# Obstacle_Bluetooth_V1_0.net
KiCad netlist of a schematic drawn in EAGLE
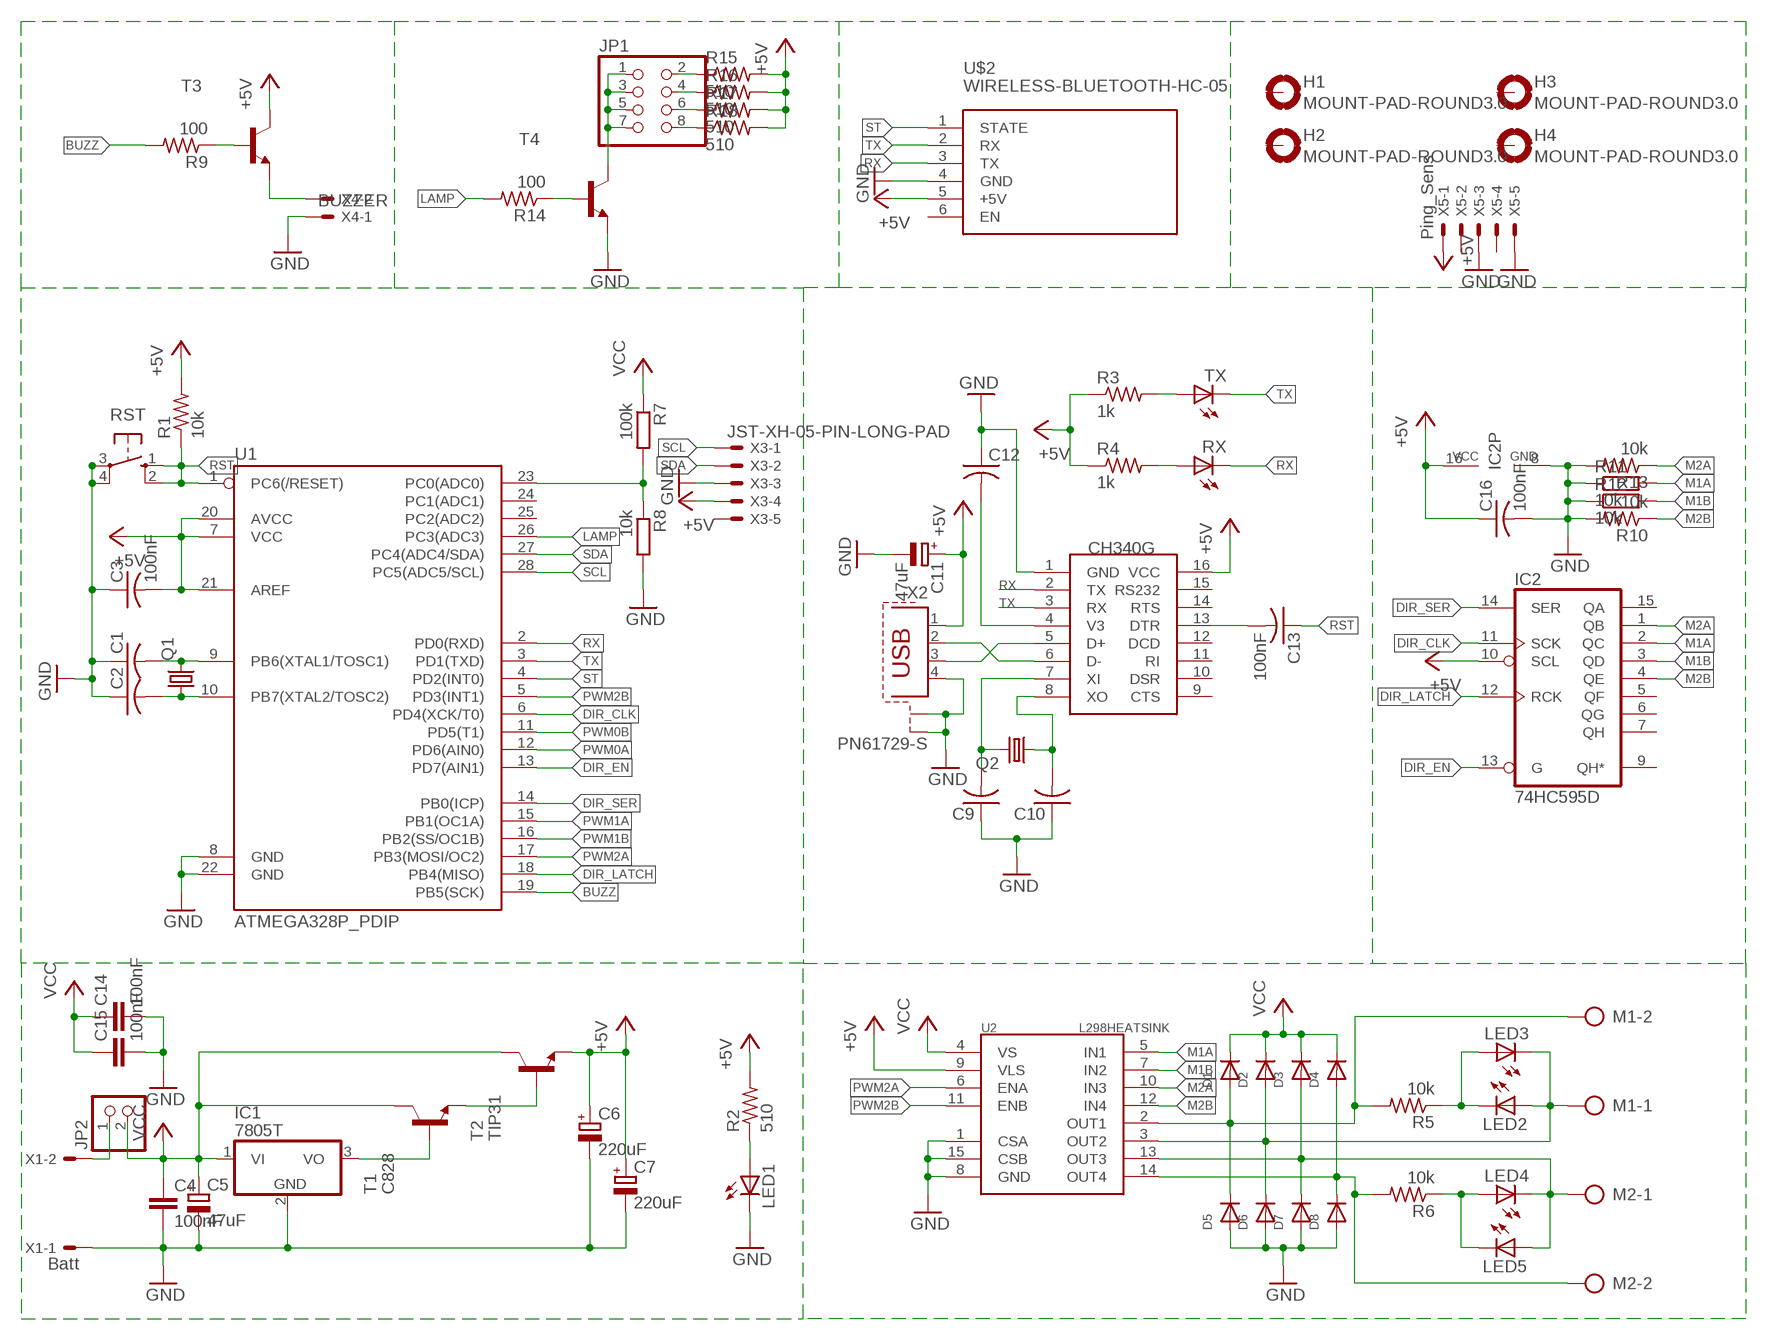
[diagram p0: schematic, sheet 1]

(export (version "E")
  (design (tool "Eeschema 10.0.6"))
  (components
    (comp (ref "C1")
      (value "C-USC0603K")
      (footprint "eagle-import:C0603K")
      (libsource (lib "eagle-import") (part "C-USC0603K"))
    )
    (comp (ref "C2")
      (value "C-USC0603K")
      (footprint "eagle-import:C0603K")
      (libsource (lib "eagle-import") (part "C-USC0603K"))
    )
    (comp (ref "C3")
      (value "100nF")
      (footprint "eagle-import:C0603K")
      (libsource (lib "eagle-import") (part "C-USC0603K"))
    )
    (comp (ref "C4")
      (value "100nF")
      (footprint "eagle-import:C5B2.5")
      (libsource (lib "eagle-import") (part "C5/2.5"))
    )
    (comp (ref "C5")
      (value "47uF")
      (footprint "eagle-import:E2,5-7")
      (libsource (lib "eagle-import") (part "CPOL-EUE2.5-7"))
    )
    (comp (ref "C6")
      (value "220uF")
      (footprint "eagle-import:E2,5-5")
      (libsource (lib "eagle-import") (part "CPOL-EUE2.5-5"))
    )
    (comp (ref "C7")
      (value "220uF")
      (footprint "eagle-import:E2,5-5")
      (libsource (lib "eagle-import") (part "CPOL-EUE2.5-5"))
    )
    (comp (ref "C9")
      (value "C-USC0603K")
      (footprint "eagle-import:C0603K")
      (libsource (lib "eagle-import") (part "C-USC0603K"))
    )
    (comp (ref "C10")
      (value "C-USC0603K")
      (footprint "eagle-import:C0603K")
      (libsource (lib "eagle-import") (part "C-USC0603K"))
    )
    (comp (ref "C11")
      (value "47uF")
      (footprint "eagle-import:E2,5-7")
      (libsource (lib "eagle-import") (part "CPOL-EUE2.5-7"))
    )
    (comp (ref "C12")
      (value "C-USC0603K")
      (footprint "eagle-import:C0603K")
      (libsource (lib "eagle-import") (part "C-USC0603K"))
    )
    (comp (ref "C13")
      (value "100nF")
      (footprint "eagle-import:C0603K")
      (libsource (lib "eagle-import") (part "C-USC0603K"))
    )
    (comp (ref "C14")
      (value "100nF")
      (footprint "eagle-import:C5B2.5")
      (libsource (lib "eagle-import") (part "C5/2.5"))
    )
    (comp (ref "C15")
      (value "100nF")
      (footprint "eagle-import:C5B2.5")
      (libsource (lib "eagle-import") (part "C5/2.5"))
    )
    (comp (ref "C16")
      (value "100nF")
      (footprint "eagle-import:C0603K")
      (libsource (lib "eagle-import") (part "C-USC0603K"))
    )
    (comp (ref "D1")
      (value "DIODESMA")
      (footprint "eagle-import:SMADIODE")
      (libsource (lib "eagle-import") (part "DIODESMA"))
    )
    (comp (ref "D2")
      (value "DIODESMA")
      (footprint "eagle-import:SMADIODE")
      (libsource (lib "eagle-import") (part "DIODESMA"))
    )
    (comp (ref "D3")
      (value "DIODESMA")
      (footprint "eagle-import:SMADIODE")
      (libsource (lib "eagle-import") (part "DIODESMA"))
    )
    (comp (ref "D4")
      (value "DIODESMA")
      (footprint "eagle-import:SMADIODE")
      (libsource (lib "eagle-import") (part "DIODESMA"))
    )
    (comp (ref "D5")
      (value "DIODESMA")
      (footprint "eagle-import:SMADIODE")
      (libsource (lib "eagle-import") (part "DIODESMA"))
    )
    (comp (ref "D6")
      (value "DIODESMA")
      (footprint "eagle-import:SMADIODE")
      (libsource (lib "eagle-import") (part "DIODESMA"))
    )
    (comp (ref "D7")
      (value "DIODESMA")
      (footprint "eagle-import:SMADIODE")
      (libsource (lib "eagle-import") (part "DIODESMA"))
    )
    (comp (ref "D8")
      (value "DIODESMA")
      (footprint "eagle-import:SMADIODE")
      (libsource (lib "eagle-import") (part "DIODESMA"))
    )
    (comp (ref "H1")
      (value "MOUNT-PAD-ROUND3.0")
      (footprint "eagle-import:3,0-PAD")
      (libsource (lib "eagle-import") (part "MOUNT-PAD-ROUND3.0"))
    )
    (comp (ref "H2")
      (value "MOUNT-PAD-ROUND3.0")
      (footprint "eagle-import:3,0-PAD")
      (libsource (lib "eagle-import") (part "MOUNT-PAD-ROUND3.0"))
    )
    (comp (ref "H3")
      (value "MOUNT-PAD-ROUND3.0")
      (footprint "eagle-import:3,0-PAD")
      (libsource (lib "eagle-import") (part "MOUNT-PAD-ROUND3.0"))
    )
    (comp (ref "H4")
      (value "MOUNT-PAD-ROUND3.0")
      (footprint "eagle-import:3,0-PAD")
      (libsource (lib "eagle-import") (part "MOUNT-PAD-ROUND3.0"))
    )
    (comp (ref "IC1")
      (value "7805T")
      (footprint "eagle-import:TO220H")
      (libsource (lib "eagle-import") (part "78T05"))
    )
    (comp (ref "IC2")
      (value "74HC595D")
      (footprint "eagle-import:SO16")
      (libsource (lib "eagle-import") (part "74595DHC"))
    )
    (comp (ref "JP1")
      (value "PINHD-2X4")
      (footprint "eagle-import:2X04")
      (libsource (lib "eagle-import") (part "PINHD-2X4"))
    )
    (comp (ref "JP2")
      (value "PINHD-1X2")
      (footprint "eagle-import:1X02")
      (libsource (lib "eagle-import") (part "PINHD-1X2"))
    )
    (comp (ref "LED1")
      (value "LED3MM")
      (footprint "eagle-import:LED3MM")
      (libsource (lib "eagle-import") (part "LED3MM"))
    )
    (comp (ref "LED2")
      (value "LED3MM")
      (footprint "eagle-import:LED3MM")
      (libsource (lib "eagle-import") (part "LED3MM"))
    )
    (comp (ref "LED3")
      (value "LED3MM")
      (footprint "eagle-import:LED3MM")
      (libsource (lib "eagle-import") (part "LED3MM"))
    )
    (comp (ref "LED4")
      (value "LED3MM")
      (footprint "eagle-import:LED3MM")
      (libsource (lib "eagle-import") (part "LED3MM"))
    )
    (comp (ref "LED5")
      (value "LED3MM")
      (footprint "eagle-import:LED3MM")
      (libsource (lib "eagle-import") (part "LED3MM"))
    )
    (comp (ref "M1")
      (value "AK500/2")
      (footprint "eagle-import:AK500_2")
      (libsource (lib "eagle-import") (part "AK500/2"))
    )
    (comp (ref "M2")
      (value "AK500/2")
      (footprint "eagle-import:AK500_2")
      (libsource (lib "eagle-import") (part "AK500/2"))
    )
    (comp (ref "Q1")
      (value "CRYSTALHC49U-V")
      (footprint "eagle-import:HC49U-V")
      (libsource (lib "eagle-import") (part "CRYSTALHC49U-V"))
    )
    (comp (ref "Q2")
      (value "CRYSTALHC49U-V")
      (footprint "eagle-import:HC49U-V")
      (libsource (lib "eagle-import") (part "CRYSTALHC49U-V"))
    )
    (comp (ref "R1")
      (value "10k")
      (footprint "eagle-import:R0603")
      (libsource (lib "eagle-import") (part "R-US_R0603"))
    )
    (comp (ref "R2")
      (value "510")
      (footprint "eagle-import:R0603")
      (libsource (lib "eagle-import") (part "R-US_R0603"))
    )
    (comp (ref "R3")
      (value "1k")
      (footprint "eagle-import:R0603")
      (libsource (lib "eagle-import") (part "R-US_R0603"))
    )
    (comp (ref "R4")
      (value "1k")
      (footprint "eagle-import:R0603")
      (libsource (lib "eagle-import") (part "R-US_R0603"))
    )
    (comp (ref "R5")
      (value "10k")
      (footprint "eagle-import:R0603")
      (libsource (lib "eagle-import") (part "R-US_R0603"))
    )
    (comp (ref "R6")
      (value "10k")
      (footprint "eagle-import:R0603")
      (libsource (lib "eagle-import") (part "R-US_R0603"))
    )
    (comp (ref "R7")
      (value "100k")
      (footprint "eagle-import:0207_7")
      (libsource (lib "eagle-import") (part "R-EU_0207/7"))
    )
    (comp (ref "R8")
      (value "10k")
      (footprint "eagle-import:0207_7")
      (libsource (lib "eagle-import") (part "R-EU_0207/7"))
    )
    (comp (ref "R9")
      (value "100")
      (footprint "eagle-import:R0603")
      (libsource (lib "eagle-import") (part "R-US_R0603"))
    )
    (comp (ref "R10")
      (value "10k")
      (footprint "eagle-import:R0603")
      (libsource (lib "eagle-import") (part "R-US_R0603"))
    )
    (comp (ref "R11")
      (value "10k")
      (footprint "eagle-import:0207_7")
      (libsource (lib "eagle-import") (part "R-EU_0207/7"))
    )
    (comp (ref "R12")
      (value "10k")
      (footprint "eagle-import:0207_7")
      (libsource (lib "eagle-import") (part "R-EU_0207/7"))
    )
    (comp (ref "R13")
      (value "10k")
      (footprint "eagle-import:R0603")
      (libsource (lib "eagle-import") (part "R-US_R0603"))
    )
    (comp (ref "R14")
      (value "100")
      (footprint "eagle-import:R0603")
      (libsource (lib "eagle-import") (part "R-US_R0603"))
    )
    (comp (ref "R15")
      (value "510")
      (footprint "eagle-import:R0603")
      (libsource (lib "eagle-import") (part "R-US_R0603"))
    )
    (comp (ref "R16")
      (value "510")
      (footprint "eagle-import:R0603")
      (libsource (lib "eagle-import") (part "R-US_R0603"))
    )
    (comp (ref "R17")
      (value "510")
      (footprint "eagle-import:R0603")
      (libsource (lib "eagle-import") (part "R-US_R0603"))
    )
    (comp (ref "R18")
      (value "510")
      (footprint "eagle-import:R0603")
      (libsource (lib "eagle-import") (part "R-US_R0603"))
    )
    (comp (ref "RST")
      (value "10-XX")
      (footprint "eagle-import:B3F-10XX")
      (fields (field (name "MPN") "B3F-1000"))
      (libsource (lib "eagle-import") (part "10-XX"))
    )
    (comp (ref "RX")
      (value "LED3MM")
      (footprint "eagle-import:LED3MM")
      (libsource (lib "eagle-import") (part "LED3MM"))
    )
    (comp (ref "T1")
      (value "C828")
      (footprint "eagle-import:TO92-ECB")
      (libsource (lib "eagle-import") (part "2SC945"))
    )
    (comp (ref "T2")
      (value "TIP31")
      (footprint "eagle-import:TO220")
      (libsource (lib "eagle-import") (part "TIP31"))
    )
    (comp (ref "T3")
      (value "-NPN-TO92L")
      (footprint "eagle-import:TO92L")
      (libsource (lib "eagle-import") (part "-NPN-TO92L"))
    )
    (comp (ref "T4")
      (value "-NPN-TO92L")
      (footprint "eagle-import:TO92L")
      (libsource (lib "eagle-import") (part "-NPN-TO92L"))
    )
    (comp (ref "TX")
      (value "LED3MM")
      (footprint "eagle-import:LED3MM")
      (libsource (lib "eagle-import") (part "LED3MM"))
    )
    (comp (ref "U$1")
      (value "CH340G")
      (footprint "eagle-import:SOIC16")
      (libsource (lib "eagle-import") (part "CH340G"))
    )
    (comp (ref "U$2")
      (value "WIRELESS-BLUETOOTH-HC-05")
      (footprint "eagle-import:WIRELESS-BLUETOOTH-HC-05")
      (libsource (lib "eagle-import") (part "WIRELESS-BLUETOOTH-HC-05"))
    )
    (comp (ref "U1")
      (value "ATMEGA328P_PDIP")
      (footprint "eagle-import:DIL28-3")
      (libsource (lib "eagle-import") (part "ATMEGA328P_PDIP"))
    )
    (comp (ref "U2")
      (value "L298HEATSINK")
      (footprint "eagle-import:MULTIWATT15_6400BGHEATSINK")
      (libsource (lib "eagle-import") (part "L298HEATSINK"))
    )
    (comp (ref "X1")
      (value "Batt")
      (footprint "eagle-import:JST-XH-02-PACKAGE-LONG-PAD")
      (libsource (lib "eagle-import") (part "JST-XH-02-PIN-LONG-PAD"))
    )
    (comp (ref "X2")
      (value "PN61729-S")
      (footprint "eagle-import:PN61729-S")
      (libsource (lib "eagle-import") (part "PN61729-S"))
    )
    (comp (ref "X3")
      (value "JST-XH-05-PIN-LONG-PAD")
      (footprint "eagle-import:JST-XH-05-PACKAGE-LONG-PAD")
      (libsource (lib "eagle-import") (part "JST-XH-05-PIN-LONG-PAD"))
    )
    (comp (ref "X4")
      (value "BUZZER")
      (footprint "eagle-import:JST-XH-02-PACKAGE-LONG-PAD")
      (libsource (lib "eagle-import") (part "JST-XH-02-PIN-LONG-PAD"))
    )
    (comp (ref "X5")
      (value "Ping_Sens")
      (footprint "eagle-import:JST-XH-05-PACKAGE-LONG-PAD")
      (libsource (lib "eagle-import") (part "JST-XH-05-PIN-LONG-PAD"))
    )
  )
  (nets
    (net (code "1") (name "+5V") (class "Default")
      (node (ref "C11") (pin "+") (pinfunction "+_+") (pintype "passive"))
      (node (ref "C16") (pin "1") (pinfunction "1_1") (pintype "passive"))
      (node (ref "C3") (pin "2") (pinfunction "2_2") (pintype "passive"))
      (node (ref "C6") (pin "+") (pinfunction "+_+") (pintype "passive"))
      (node (ref "C7") (pin "+") (pinfunction "+_+") (pintype "passive"))
      (node (ref "IC2") (pin "10") (pinfunction "SCL_10") (pintype "input"))
      (node (ref "IC2") (pin "16") (pinfunction "VCC_16") (pintype "power_in"))
      (node (ref "R1") (pin "2") (pinfunction "2_2") (pintype "passive"))
      (node (ref "R15") (pin "2") (pinfunction "2_2") (pintype "passive"))
      (node (ref "R16") (pin "2") (pinfunction "2_2") (pintype "passive"))
      (node (ref "R17") (pin "2") (pinfunction "2_2") (pintype "passive"))
      (node (ref "R18") (pin "2") (pinfunction "2_2") (pintype "passive"))
      (node (ref "R2") (pin "2") (pinfunction "2_2") (pintype "passive"))
      (node (ref "R3") (pin "1") (pinfunction "1_1") (pintype "passive"))
      (node (ref "R4") (pin "1") (pinfunction "1_1") (pintype "passive"))
      (node (ref "T2") (pin "3") (pinfunction "E_3") (pintype "passive"))
      (node (ref "T3") (pin "3") (pinfunction "C_3") (pintype "passive"))
      (node (ref "U$1") (pin "16") (pinfunction "VCC_16") (pintype "bidirectional"))
      (node (ref "U$2") (pin "5") (pinfunction "+5V_5") (pintype "power_in"))
      (node (ref "U1") (pin "20") (pinfunction "AVCC_20") (pintype "bidirectional"))
      (node (ref "U1") (pin "21") (pinfunction "AREF_21") (pintype "bidirectional"))
      (node (ref "U1") (pin "7") (pinfunction "VCC_7") (pintype "bidirectional"))
      (node (ref "U2") (pin "9") (pinfunction "VLS_9") (pintype "bidirectional"))
      (node (ref "X2") (pin "1") (pinfunction "1_1") (pintype "passive"))
      (node (ref "X3") (pin "4") (pinfunction "S_4") (pintype "passive"))
      (node (ref "X5") (pin "1") (pinfunction "S_1") (pintype "passive"))
    )
    (net (code "2") (name "BUZZ") (class "Default")
      (node (ref "R9") (pin "2") (pinfunction "2_2") (pintype "passive"))
      (node (ref "U1") (pin "19") (pinfunction "PB5(SCK)_19") (pintype "bidirectional"))
    )
    (net (code "3") (name "DIR_CLK") (class "Default")
      (node (ref "IC2") (pin "11") (pinfunction "SCK_11") (pintype "input"))
      (node (ref "U1") (pin "6") (pinfunction "PD4(XCK/T0)_6") (pintype "bidirectional"))
    )
    (net (code "4") (name "DIR_EN") (class "Default")
      (node (ref "IC2") (pin "13") (pinfunction "G_13") (pintype "input"))
      (node (ref "U1") (pin "13") (pinfunction "PD7(AIN1)_13") (pintype "bidirectional"))
    )
    (net (code "5") (name "DIR_LATCH") (class "Default")
      (node (ref "IC2") (pin "12") (pinfunction "RCK_12") (pintype "input"))
      (node (ref "U1") (pin "18") (pinfunction "PB4(MISO)_18") (pintype "bidirectional"))
    )
    (net (code "6") (name "DIR_SER") (class "Default")
      (node (ref "IC2") (pin "14") (pinfunction "SER_14") (pintype "input"))
      (node (ref "U1") (pin "14") (pinfunction "PB0(ICP)_14") (pintype "bidirectional"))
    )
    (net (code "7") (name "GND") (class "Default")
      (node (ref "C1") (pin "1") (pinfunction "1_1") (pintype "passive"))
      (node (ref "C10") (pin "1") (pinfunction "1_1") (pintype "passive"))
      (node (ref "C11") (pin "-") (pinfunction "-_-") (pintype "passive"))
      (node (ref "C12") (pin "1") (pinfunction "1_1") (pintype "passive"))
      (node (ref "C14") (pin "2") (pinfunction "2_2") (pintype "passive"))
      (node (ref "C15") (pin "2") (pinfunction "2_2") (pintype "passive"))
      (node (ref "C16") (pin "2") (pinfunction "2_2") (pintype "passive"))
      (node (ref "C2") (pin "1") (pinfunction "1_1") (pintype "passive"))
      (node (ref "C3") (pin "1") (pinfunction "1_1") (pintype "passive"))
      (node (ref "C4") (pin "2") (pinfunction "2_2") (pintype "passive"))
      (node (ref "C5") (pin "-") (pinfunction "-_-") (pintype "passive"))
      (node (ref "C6") (pin "-") (pinfunction "-_-") (pintype "passive"))
      (node (ref "C7") (pin "-") (pinfunction "-_-") (pintype "passive"))
      (node (ref "C9") (pin "1") (pinfunction "1_1") (pintype "passive"))
      (node (ref "D5") (pin "A") (pinfunction "A_A") (pintype "passive"))
      (node (ref "D6") (pin "A") (pinfunction "A_A") (pintype "passive"))
      (node (ref "D7") (pin "A") (pinfunction "A_A") (pintype "passive"))
      (node (ref "D8") (pin "A") (pinfunction "A_A") (pintype "passive"))
      (node (ref "IC1") (pin "2") (pinfunction "GND_2") (pintype "passive"))
      (node (ref "IC2") (pin "8") (pinfunction "GND_8") (pintype "power_in"))
      (node (ref "LED1") (pin "K") (pinfunction "C_K") (pintype "passive"))
      (node (ref "R10") (pin "2") (pinfunction "2_2") (pintype "passive"))
      (node (ref "R11") (pin "1") (pinfunction "1_1") (pintype "passive"))
      (node (ref "R12") (pin "1") (pinfunction "1_1") (pintype "passive"))
      (node (ref "R13") (pin "2") (pinfunction "2_2") (pintype "passive"))
      (node (ref "R8") (pin "2") (pinfunction "2_2") (pintype "passive"))
      (node (ref "RST") (pin "3") (pinfunction "P_3") (pintype "passive"))
      (node (ref "RST") (pin "4") (pinfunction "P1_4") (pintype "passive"))
      (node (ref "T4") (pin "1") (pinfunction "E_1") (pintype "passive"))
      (node (ref "U$1") (pin "1") (pinfunction "GND_1") (pintype "bidirectional"))
      (node (ref "U$2") (pin "4") (pinfunction "GND_4") (pintype "power_in"))
      (node (ref "U1") (pin "22") (pinfunction "GND_22") (pintype "bidirectional"))
      (node (ref "U1") (pin "8") (pinfunction "GND_8") (pintype "bidirectional"))
      (node (ref "U2") (pin "1") (pinfunction "CSA_1") (pintype "bidirectional"))
      (node (ref "U2") (pin "15") (pinfunction "CSB_15") (pintype "bidirectional"))
      (node (ref "U2") (pin "8") (pinfunction "GND_8") (pintype "bidirectional"))
      (node (ref "X1") (pin "1") (pinfunction "S_1") (pintype "passive"))
      (node (ref "X2") (pin "4") (pinfunction "4_4") (pintype "passive"))
      (node (ref "X2") (pin "S1") (pinfunction "S1_S1") (pintype "passive"))
      (node (ref "X2") (pin "S2") (pinfunction "S2_S2") (pintype "passive"))
      (node (ref "X3") (pin "3") (pinfunction "S_3") (pintype "passive"))
      (node (ref "X4") (pin "1") (pinfunction "S_1") (pintype "passive"))
      (node (ref "X5") (pin "3") (pinfunction "S_3") (pintype "passive"))
      (node (ref "X5") (pin "5") (pinfunction "S_5") (pintype "passive"))
    )
    (net (code "8") (name "LAMP") (class "Default")
      (node (ref "R14") (pin "2") (pinfunction "2_2") (pintype "passive"))
      (node (ref "U1") (pin "26") (pinfunction "PC3(ADC3)_26") (pintype "bidirectional"))
    )
    (net (code "9") (name "M1A") (class "Default")
      (node (ref "IC2") (pin "2") (pinfunction "QC_2") (pintype "tri_state"))
      (node (ref "R11") (pin "2") (pinfunction "2_2") (pintype "passive"))
      (node (ref "U2") (pin "5") (pinfunction "IN1_5") (pintype "bidirectional"))
    )
    (net (code "10") (name "M1B") (class "Default")
      (node (ref "IC2") (pin "3") (pinfunction "QD_3") (pintype "tri_state"))
      (node (ref "R12") (pin "2") (pinfunction "2_2") (pintype "passive"))
      (node (ref "U2") (pin "7") (pinfunction "IN2_7") (pintype "bidirectional"))
    )
    (net (code "11") (name "M2A") (class "Default")
      (node (ref "IC2") (pin "1") (pinfunction "QB_1") (pintype "tri_state"))
      (node (ref "R13") (pin "1") (pinfunction "1_1") (pintype "passive"))
      (node (ref "U2") (pin "10") (pinfunction "IN3_10") (pintype "bidirectional"))
    )
    (net (code "12") (name "M2B") (class "Default")
      (node (ref "IC2") (pin "4") (pinfunction "QE_4") (pintype "tri_state"))
      (node (ref "R10") (pin "1") (pinfunction "1_1") (pintype "passive"))
      (node (ref "U2") (pin "12") (pinfunction "IN4_12") (pintype "bidirectional"))
    )
    (net (code "13") (name "Net-(IC1-VO)") (class "Default")
      (node (ref "IC1") (pin "3") (pinfunction "VO_3") (pintype "passive"))
      (node (ref "T1") (pin "B") (pinfunction "B_B") (pintype "passive"))
    )
    (net (code "14") (name "Net-(JP1-Pad2)") (class "Default")
      (node (ref "JP1") (pin "2") (pinfunction "2_2") (pintype "passive"))
      (node (ref "R15") (pin "1") (pinfunction "1_1") (pintype "passive"))
    )
    (net (code "15") (name "Net-(JP1-Pad4)") (class "Default")
      (node (ref "JP1") (pin "4") (pinfunction "4_4") (pintype "passive"))
      (node (ref "R16") (pin "1") (pinfunction "1_1") (pintype "passive"))
    )
    (net (code "16") (name "Net-(JP1-Pad6)") (class "Default")
      (node (ref "JP1") (pin "6") (pinfunction "6_6") (pintype "passive"))
      (node (ref "R17") (pin "1") (pinfunction "1_1") (pintype "passive"))
    )
    (net (code "17") (name "Net-(JP1-Pad8)") (class "Default")
      (node (ref "JP1") (pin "8") (pinfunction "8_8") (pintype "passive"))
      (node (ref "R18") (pin "1") (pinfunction "1_1") (pintype "passive"))
    )
    (net (code "18") (name "Net-(LED1-PadA)") (class "Default")
      (node (ref "LED1") (pin "A") (pinfunction "A_A") (pintype "passive"))
      (node (ref "R2") (pin "1") (pinfunction "1_1") (pintype "passive"))
    )
    (net (code "19") (name "Net-(LED2-C)") (class "Default")
      (node (ref "LED2") (pin "K") (pinfunction "C_K") (pintype "passive"))
      (node (ref "LED3") (pin "A") (pinfunction "A_A") (pintype "passive"))
      (node (ref "R5") (pin "1") (pinfunction "1_1") (pintype "passive"))
    )
    (net (code "20") (name "Net-(LED3-C)") (class "Default")
      (node (ref "D2") (pin "A") (pinfunction "A_A") (pintype "passive"))
      (node (ref "D6") (pin "C") (pinfunction "C_C") (pintype "passive"))
      (node (ref "LED2") (pin "A") (pinfunction "A_A") (pintype "passive"))
      (node (ref "LED3") (pin "K") (pinfunction "C_K") (pintype "passive"))
      (node (ref "M1") (pin "1") (pinfunction "KL_1") (pintype "passive"))
      (node (ref "U2") (pin "3") (pinfunction "OUT2_3") (pintype "bidirectional"))
    )
    (net (code "21") (name "Net-(LED4-C)") (class "Default")
      (node (ref "D3") (pin "A") (pinfunction "A_A") (pintype "passive"))
      (node (ref "D7") (pin "C") (pinfunction "C_C") (pintype "passive"))
      (node (ref "LED4") (pin "K") (pinfunction "C_K") (pintype "passive"))
      (node (ref "LED5") (pin "A") (pinfunction "A_A") (pintype "passive"))
      (node (ref "M2") (pin "1") (pinfunction "KL_1") (pintype "passive"))
      (node (ref "U2") (pin "13") (pinfunction "OUT3_13") (pintype "bidirectional"))
    )
    (net (code "22") (name "Net-(LED5-C)") (class "Default")
      (node (ref "LED4") (pin "A") (pinfunction "A_A") (pintype "passive"))
      (node (ref "LED5") (pin "K") (pinfunction "C_K") (pintype "passive"))
      (node (ref "R6") (pin "1") (pinfunction "1_1") (pintype "passive"))
    )
    (net (code "23") (name "Net-(M1B-KL)") (class "Default")
      (node (ref "D1") (pin "A") (pinfunction "A_A") (pintype "passive"))
      (node (ref "D5") (pin "C") (pinfunction "C_C") (pintype "passive"))
      (node (ref "M1") (pin "2") (pinfunction "KL_2") (pintype "passive"))
      (node (ref "R5") (pin "2") (pinfunction "2_2") (pintype "passive"))
      (node (ref "U2") (pin "2") (pinfunction "OUT1_2") (pintype "bidirectional"))
    )
    (net (code "24") (name "Net-(M2B-KL)") (class "Default")
      (node (ref "D4") (pin "A") (pinfunction "A_A") (pintype "passive"))
      (node (ref "D8") (pin "C") (pinfunction "C_C") (pintype "passive"))
      (node (ref "M2") (pin "2") (pinfunction "KL_2") (pintype "passive"))
      (node (ref "R6") (pin "2") (pinfunction "2_2") (pintype "passive"))
      (node (ref "U2") (pin "14") (pinfunction "OUT4_14") (pintype "bidirectional"))
    )
    (net (code "25") (name "Net-(R3-Pad2)") (class "Default")
      (node (ref "R3") (pin "2") (pinfunction "2_2") (pintype "passive"))
      (node (ref "TX") (pin "A") (pinfunction "A_A") (pintype "passive"))
    )
    (net (code "26") (name "Net-(R4-Pad2)") (class "Default")
      (node (ref "R4") (pin "2") (pinfunction "2_2") (pintype "passive"))
      (node (ref "RX") (pin "A") (pinfunction "A_A") (pintype "passive"))
    )
    (net (code "27") (name "Net-(T2-B)") (class "Default")
      (node (ref "T1") (pin "E") (pinfunction "E_E") (pintype "passive"))
      (node (ref "T2") (pin "1") (pinfunction "B_1") (pintype "passive"))
    )
    (net (code "28") (name "Net-(T3-B)") (class "Default")
      (node (ref "R9") (pin "1") (pinfunction "1_1") (pintype "passive"))
      (node (ref "T3") (pin "2") (pinfunction "B_2") (pintype "passive"))
    )
    (net (code "29") (name "Net-(T3-E)") (class "Default")
      (node (ref "T3") (pin "1") (pinfunction "E_1") (pintype "passive"))
      (node (ref "X4") (pin "2") (pinfunction "S_2") (pintype "passive"))
    )
    (net (code "30") (name "Net-(T4-B)") (class "Default")
      (node (ref "R14") (pin "1") (pinfunction "1_1") (pintype "passive"))
      (node (ref "T4") (pin "2") (pinfunction "B_2") (pintype "passive"))
    )
    (net (code "31") (name "Net-(T4-C)") (class "Default")
      (node (ref "JP1") (pin "1") (pinfunction "1_1") (pintype "passive"))
      (node (ref "JP1") (pin "3") (pinfunction "3_3") (pintype "passive"))
      (node (ref "JP1") (pin "5") (pinfunction "5_5") (pintype "passive"))
      (node (ref "JP1") (pin "7") (pinfunction "7_7") (pintype "passive"))
      (node (ref "T4") (pin "3") (pinfunction "C_3") (pintype "passive"))
    )
    (net (code "32") (name "Net-(U$1-D+)") (class "Default")
      (node (ref "U$1") (pin "5") (pinfunction "D+_5") (pintype "bidirectional"))
      (node (ref "X2") (pin "3") (pinfunction "3_3") (pintype "passive"))
    )
    (net (code "33") (name "Net-(U$1-D-)") (class "Default")
      (node (ref "U$1") (pin "6") (pinfunction "D-_6") (pintype "bidirectional"))
      (node (ref "X2") (pin "2") (pinfunction "2_2") (pintype "passive"))
    )
    (net (code "34") (name "Net-(U$1-DTR)") (class "Default")
      (node (ref "C13") (pin "2") (pinfunction "2_2") (pintype "passive"))
      (node (ref "U$1") (pin "13") (pinfunction "DTR_13") (pintype "bidirectional"))
    )
    (net (code "35") (name "Net-(U$1-V3)") (class "Default")
      (node (ref "C12") (pin "2") (pinfunction "2_2") (pintype "passive"))
      (node (ref "U$1") (pin "4") (pinfunction "V3_4") (pintype "bidirectional"))
    )
    (net (code "36") (name "Net-(U$1-XI)") (class "Default")
      (node (ref "C9") (pin "2") (pinfunction "2_2") (pintype "passive"))
      (node (ref "Q2") (pin "2") (pinfunction "2_2") (pintype "passive"))
      (node (ref "U$1") (pin "7") (pinfunction "XI_7") (pintype "bidirectional"))
    )
    (net (code "37") (name "Net-(U$1-XO)") (class "Default")
      (node (ref "C10") (pin "2") (pinfunction "2_2") (pintype "passive"))
      (node (ref "Q2") (pin "1") (pinfunction "1_1") (pintype "passive"))
      (node (ref "U$1") (pin "8") (pinfunction "XO_8") (pintype "bidirectional"))
    )
    (net (code "38") (name "Net-(U1-PB6(XTAL1{slash}TOSC1))") (class "Default")
      (node (ref "C1") (pin "2") (pinfunction "2_2") (pintype "passive"))
      (node (ref "Q1") (pin "2") (pinfunction "2_2") (pintype "passive"))
      (node (ref "U1") (pin "9") (pinfunction "PB6(XTAL1/TOSC1)_9") (pintype "bidirectional"))
    )
    (net (code "39") (name "Net-(U1-PB7(XTAL2{slash}TOSC2))") (class "Default")
      (node (ref "C2") (pin "2") (pinfunction "2_2") (pintype "passive"))
      (node (ref "Q1") (pin "1") (pinfunction "1_1") (pintype "passive"))
      (node (ref "U1") (pin "10") (pinfunction "PB7(XTAL2/TOSC2)_10") (pintype "bidirectional"))
    )
    (net (code "40") (name "Net-(U1-PC0(ADC0))") (class "Default")
      (node (ref "R7") (pin "2") (pinfunction "2_2") (pintype "passive"))
      (node (ref "R8") (pin "1") (pinfunction "1_1") (pintype "passive"))
      (node (ref "U1") (pin "23") (pinfunction "PC0(ADC0)_23") (pintype "bidirectional"))
    )
    (net (code "41") (name "Net-(X1B-S)") (class "Default")
      (node (ref "JP2") (pin "1") (pinfunction "1_1") (pintype "passive"))
      (node (ref "X1") (pin "2") (pinfunction "S_2") (pintype "passive"))
    )
    (net (code "42") (name "PWM0A") (class "Default")
      (node (ref "U1") (pin "12") (pinfunction "PD6(AIN0)_12") (pintype "bidirectional"))
    )
    (net (code "43") (name "PWM0B") (class "Default")
      (node (ref "U1") (pin "11") (pinfunction "PD5(T1)_11") (pintype "bidirectional"))
    )
    (net (code "44") (name "PWM1A") (class "Default")
      (node (ref "U1") (pin "15") (pinfunction "PB1(OC1A)_15") (pintype "bidirectional"))
    )
    (net (code "45") (name "PWM1B") (class "Default")
      (node (ref "U1") (pin "16") (pinfunction "PB2(SS/OC1B)_16") (pintype "bidirectional"))
    )
    (net (code "46") (name "PWM2A") (class "Default")
      (node (ref "U1") (pin "17") (pinfunction "PB3(MOSI/OC2)_17") (pintype "bidirectional"))
      (node (ref "U2") (pin "6") (pinfunction "ENA_6") (pintype "bidirectional"))
    )
    (net (code "47") (name "PWM2B") (class "Default")
      (node (ref "U1") (pin "5") (pinfunction "PD3(INT1)_5") (pintype "bidirectional"))
      (node (ref "U2") (pin "11") (pinfunction "ENB_11") (pintype "bidirectional"))
    )
    (net (code "48") (name "RST") (class "Default")
      (node (ref "C13") (pin "1") (pinfunction "1_1") (pintype "passive"))
      (node (ref "R1") (pin "1") (pinfunction "1_1") (pintype "passive"))
      (node (ref "RST") (pin "1") (pinfunction "S_1") (pintype "passive"))
      (node (ref "RST") (pin "2") (pinfunction "S1_2") (pintype "passive"))
      (node (ref "U1") (pin "1") (pinfunction "PC6(/RESET)_1") (pintype "bidirectional"))
    )
    (net (code "49") (name "RX") (class "Default")
      (node (ref "RX") (pin "K") (pinfunction "C_K") (pintype "passive"))
      (node (ref "U$1") (pin "2") (pinfunction "TX_2") (pintype "bidirectional"))
      (node (ref "U$2") (pin "3") (pinfunction "TX_3") (pintype "bidirectional"))
      (node (ref "U1") (pin "2") (pinfunction "PD0(RXD)_2") (pintype "bidirectional"))
    )
    (net (code "50") (name "SCL") (class "Default")
      (node (ref "U1") (pin "28") (pinfunction "PC5(ADC5/SCL)_28") (pintype "bidirectional"))
      (node (ref "X3") (pin "1") (pinfunction "S_1") (pintype "passive"))
    )
    (net (code "51") (name "SDA") (class "Default")
      (node (ref "U1") (pin "27") (pinfunction "PC4(ADC4/SDA)_27") (pintype "bidirectional"))
      (node (ref "X3") (pin "2") (pinfunction "S_2") (pintype "passive"))
    )
    (net (code "52") (name "ST") (class "Default")
      (node (ref "U$2") (pin "1") (pinfunction "STATE_1") (pintype "bidirectional"))
      (node (ref "U1") (pin "4") (pinfunction "PD2(INT0)_4") (pintype "bidirectional"))
    )
    (net (code "53") (name "TX") (class "Default")
      (node (ref "TX") (pin "K") (pinfunction "C_K") (pintype "passive"))
      (node (ref "U$1") (pin "3") (pinfunction "RX_3") (pintype "bidirectional"))
      (node (ref "U$2") (pin "2") (pinfunction "RX_2") (pintype "bidirectional"))
      (node (ref "U1") (pin "3") (pinfunction "PD1(TXD)_3") (pintype "bidirectional"))
    )
    (net (code "54") (name "VCC") (class "Default")
      (node (ref "C14") (pin "1") (pinfunction "1_1") (pintype "passive"))
      (node (ref "C15") (pin "1") (pinfunction "1_1") (pintype "passive"))
      (node (ref "C4") (pin "1") (pinfunction "1_1") (pintype "passive"))
      (node (ref "C5") (pin "+") (pinfunction "+_+") (pintype "passive"))
      (node (ref "D1") (pin "C") (pinfunction "C_C") (pintype "passive"))
      (node (ref "D2") (pin "C") (pinfunction "C_C") (pintype "passive"))
      (node (ref "D3") (pin "C") (pinfunction "C_C") (pintype "passive"))
      (node (ref "D4") (pin "C") (pinfunction "C_C") (pintype "passive"))
      (node (ref "IC1") (pin "1") (pinfunction "VI_1") (pintype "input"))
      (node (ref "JP2") (pin "2") (pinfunction "2_2") (pintype "passive"))
      (node (ref "R7") (pin "1") (pinfunction "1_1") (pintype "passive"))
      (node (ref "T1") (pin "C") (pinfunction "C_C") (pintype "passive"))
      (node (ref "T2") (pin "2") (pinfunction "C_2") (pintype "passive"))
      (node (ref "U2") (pin "4") (pinfunction "VS_4") (pintype "bidirectional"))
    )
    (net (code "55") (name "unconnected-(H1-MOUNT-PadB3,0)") (class "Default")
      (node (ref "H1") (pin "B3,0") (pinfunction "MOUNT_B3,0") (pintype "passive"))
    )
    (net (code "56") (name "unconnected-(H2-MOUNT-PadB3,0)") (class "Default")
      (node (ref "H2") (pin "B3,0") (pinfunction "MOUNT_B3,0") (pintype "passive"))
    )
    (net (code "57") (name "unconnected-(H3-MOUNT-PadB3,0)") (class "Default")
      (node (ref "H3") (pin "B3,0") (pinfunction "MOUNT_B3,0") (pintype "passive"))
    )
    (net (code "58") (name "unconnected-(H4-MOUNT-PadB3,0)") (class "Default")
      (node (ref "H4") (pin "B3,0") (pinfunction "MOUNT_B3,0") (pintype "passive"))
    )
    (net (code "59") (name "unconnected-(IC2A-QA-Pad15)") (class "Default")
      (node (ref "IC2") (pin "15") (pinfunction "QA_15") (pintype "tri_state"))
    )
    (net (code "60") (name "unconnected-(IC2A-QF-Pad5)") (class "Default")
      (node (ref "IC2") (pin "5") (pinfunction "QF_5") (pintype "tri_state"))
    )
    (net (code "61") (name "unconnected-(IC2A-QG-Pad6)") (class "Default")
      (node (ref "IC2") (pin "6") (pinfunction "QG_6") (pintype "tri_state"))
    )
    (net (code "62") (name "unconnected-(IC2A-QH*-Pad9)") (class "Default")
      (node (ref "IC2") (pin "9") (pinfunction "QH*_9") (pintype "tri_state"))
    )
    (net (code "63") (name "unconnected-(IC2A-QH-Pad7)") (class "Default")
      (node (ref "IC2") (pin "7") (pinfunction "QH_7") (pintype "tri_state"))
    )
    (net (code "64") (name "unconnected-(U$1-CTS-Pad9)") (class "Default")
      (node (ref "U$1") (pin "9") (pinfunction "CTS_9") (pintype "bidirectional"))
    )
    (net (code "65") (name "unconnected-(U$1-DCD-Pad12)") (class "Default")
      (node (ref "U$1") (pin "12") (pinfunction "DCD_12") (pintype "bidirectional"))
    )
    (net (code "66") (name "unconnected-(U$1-DSR-Pad10)") (class "Default")
      (node (ref "U$1") (pin "10") (pinfunction "DSR_10") (pintype "bidirectional"))
    )
    (net (code "67") (name "unconnected-(U$1-RI-Pad11)") (class "Default")
      (node (ref "U$1") (pin "11") (pinfunction "RI_11") (pintype "bidirectional"))
    )
    (net (code "68") (name "unconnected-(U$1-RS232-Pad15)") (class "Default")
      (node (ref "U$1") (pin "15") (pinfunction "RS232_15") (pintype "bidirectional"))
    )
    (net (code "69") (name "unconnected-(U$1-RTS-Pad14)") (class "Default")
      (node (ref "U$1") (pin "14") (pinfunction "RTS_14") (pintype "bidirectional"))
    )
    (net (code "70") (name "unconnected-(U$2-EN-Pad6)") (class "Default")
      (node (ref "U$2") (pin "6") (pinfunction "EN_6") (pintype "bidirectional"))
    )
    (net (code "71") (name "unconnected-(U1-PC1(ADC1)-Pad24)") (class "Default")
      (node (ref "U1") (pin "24") (pinfunction "PC1(ADC1)_24") (pintype "bidirectional"))
    )
    (net (code "72") (name "unconnected-(U1-PC2(ADC2)-Pad25)") (class "Default")
      (node (ref "U1") (pin "25") (pinfunction "PC2(ADC2)_25") (pintype "bidirectional"))
    )
    (net (code "73") (name "unconnected-(X3E-S-Pad5)") (class "Default")
      (node (ref "X3") (pin "5") (pinfunction "S_5") (pintype "passive"))
    )
    (net (code "74") (name "unconnected-(X5B-S-Pad2)") (class "Default")
      (node (ref "X5") (pin "2") (pinfunction "S_2") (pintype "passive"))
    )
    (net (code "75") (name "unconnected-(X5D-S-Pad4)") (class "Default")
      (node (ref "X5") (pin "4") (pinfunction "S_4") (pintype "passive"))
    )
  )
)
